# Muller-C3.net
KiCad netlist of a schematic drawn in Altium Designer
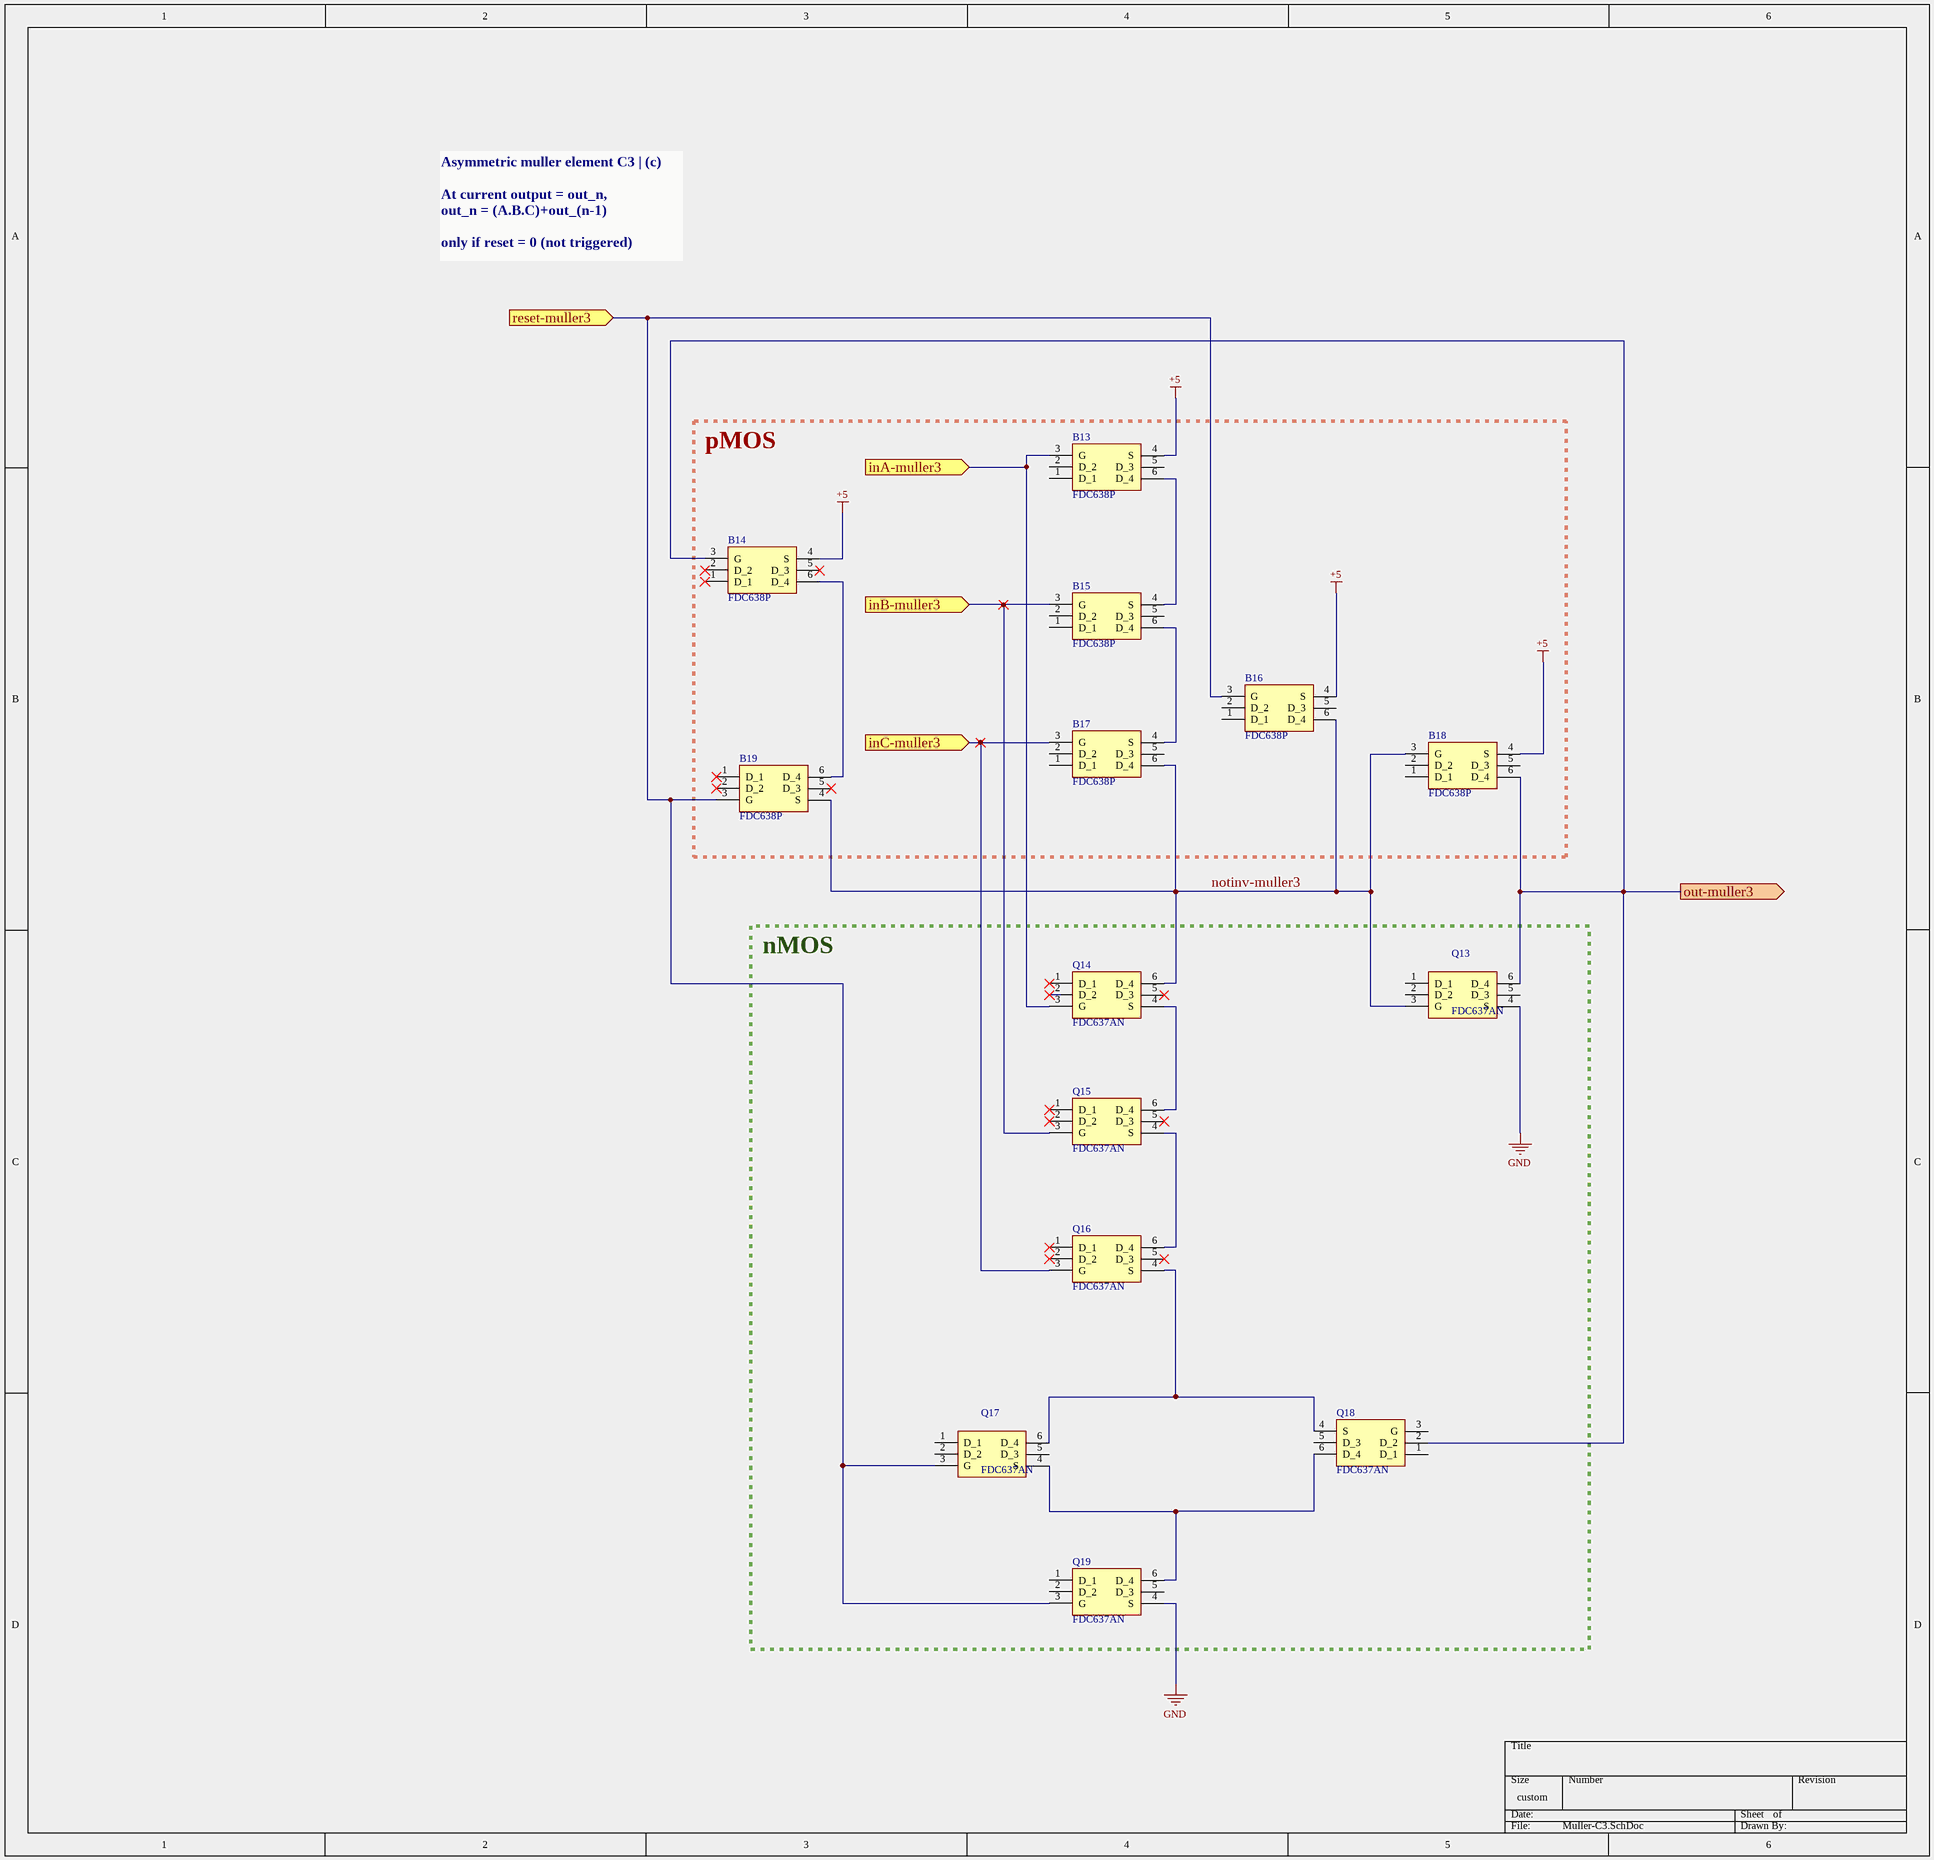
[diagram p0: Muller-C3.SchDoc]

(export (version "E")
  (design (tool "Eeschema 10.0.6"))
  (components
    (comp (ref "B13")
      (value "FDC638P")
      (footprint "SOT95P275X110-6N")
      (description "Low gate charge (10 nC typical)")
      (fields (field (name "MOUSER PART NUMBER") "512-FDC638P"))
      (libsource (lib "iloke") (part "FDC638P"))
    )
    (comp (ref "B14")
      (value "FDC638P")
      (footprint "SOT95P275X110-6N")
      (description "Low gate charge (10 nC typical)")
      (fields (field (name "MOUSER PART NUMBER") "512-FDC638P"))
      (libsource (lib "iloke") (part "FDC638P"))
    )
    (comp (ref "B15")
      (value "FDC638P")
      (footprint "SOT95P275X110-6N")
      (description "Low gate charge (10 nC typical)")
      (fields (field (name "MOUSER PART NUMBER") "512-FDC638P"))
      (libsource (lib "iloke") (part "FDC638P"))
    )
    (comp (ref "B16")
      (value "FDC638P")
      (footprint "SOT95P275X110-6N")
      (description "Low gate charge (10 nC typical)")
      (fields (field (name "MOUSER PART NUMBER") "512-FDC638P"))
      (libsource (lib "iloke") (part "FDC638P"))
    )
    (comp (ref "B17")
      (value "FDC638P")
      (footprint "SOT95P275X110-6N")
      (description "Low gate charge (10 nC typical)")
      (fields (field (name "MOUSER PART NUMBER") "512-FDC638P"))
      (libsource (lib "iloke") (part "FDC638P"))
    )
    (comp (ref "B18")
      (value "FDC638P")
      (footprint "SOT95P275X110-6N")
      (description "Low gate charge (10 nC typical)")
      (fields (field (name "MOUSER PART NUMBER") "512-FDC638P"))
      (libsource (lib "iloke") (part "FDC638P"))
    )
    (comp (ref "B19")
      (value "FDC638P")
      (footprint "SOT95P275X110-6N")
      (description "Low gate charge (10 nC typical)")
      (fields (field (name "MOUSER PART NUMBER") "512-FDC638P"))
      (libsource (lib "") (part "FDC638P_1"))
    )
    (comp (ref "Q13")
      (value "FDC637AN")
      (footprint "SOT95P275X110-6N")
      (description "Low gate charge (10.5nC typical).")
      (fields (field (name "MOUSER PART NUMBER") "512-FDC637AN"))
      (libsource (lib "iloke") (part "FDC637AN"))
    )
    (comp (ref "Q14")
      (value "FDC637AN")
      (footprint "SOT95P275X110-6N")
      (description "Low gate charge (10.5nC typical).")
      (fields (field (name "MOUSER PART NUMBER") "512-FDC637AN"))
      (libsource (lib "iloke") (part "FDC637AN"))
    )
    (comp (ref "Q15")
      (value "FDC637AN")
      (footprint "SOT95P275X110-6N")
      (description "Low gate charge (10.5nC typical).")
      (fields (field (name "MOUSER PART NUMBER") "512-FDC637AN"))
      (libsource (lib "iloke") (part "FDC637AN"))
    )
    (comp (ref "Q16")
      (value "FDC637AN")
      (footprint "SOT95P275X110-6N")
      (description "Low gate charge (10.5nC typical).")
      (fields (field (name "MOUSER PART NUMBER") "512-FDC637AN"))
      (libsource (lib "iloke") (part "FDC637AN"))
    )
    (comp (ref "Q17")
      (value "FDC637AN")
      (footprint "SOT95P275X110-6N")
      (description "Low gate charge (10.5nC typical).")
      (fields (field (name "MOUSER PART NUMBER") "512-FDC637AN"))
      (libsource (lib "iloke") (part "FDC637AN"))
    )
    (comp (ref "Q18")
      (value "FDC637AN")
      (footprint "SOT95P275X110-6N")
      (description "Low gate charge (10.5nC typical).")
      (fields (field (name "MOUSER PART NUMBER") "512-FDC637AN"))
      (libsource (lib "") (part "FDC637AN_1"))
    )
    (comp (ref "Q19")
      (value "FDC637AN")
      (footprint "SOT95P275X110-6N")
      (description "Low gate charge (10.5nC typical).")
      (fields (field (name "MOUSER PART NUMBER") "512-FDC637AN"))
      (libsource (lib "iloke") (part "FDC637AN"))
    )
  )
  (nets
    (net (code "1") (name "+5") (class "Default")
      (node (ref "B13") (pin "4") (pinfunction "S_4") (pintype "passive"))
      (node (ref "B14") (pin "4") (pinfunction "S_4") (pintype "passive"))
      (node (ref "B16") (pin "4") (pinfunction "S_4") (pintype "passive"))
      (node (ref "B18") (pin "4") (pinfunction "S_4") (pintype "passive"))
    )
    (net (code "2") (name "/inA-muller3") (class "Default")
      (node (ref "B13") (pin "3") (pinfunction "G_3") (pintype "passive"))
      (node (ref "Q14") (pin "3") (pinfunction "G_3") (pintype "passive"))
    )
    (net (code "3") (name "/inB-muller3") (class "Default")
      (node (ref "B15") (pin "3") (pinfunction "G_3") (pintype "passive"))
      (node (ref "Q15") (pin "3") (pinfunction "G_3") (pintype "passive"))
    )
    (net (code "4") (name "/inC-muller3") (class "Default")
      (node (ref "B17") (pin "3") (pinfunction "G_3") (pintype "passive"))
      (node (ref "Q16") (pin "3") (pinfunction "G_3") (pintype "passive"))
    )
    (net (code "5") (name "/notinv-muller3") (class "Default")
      (node (ref "B16") (pin "6") (pinfunction "D_4_6") (pintype "passive"))
      (node (ref "B17") (pin "6") (pinfunction "D_4_6") (pintype "passive"))
      (node (ref "B18") (pin "3") (pinfunction "G_3") (pintype "passive"))
      (node (ref "B19") (pin "4") (pinfunction "S_4") (pintype "passive"))
      (node (ref "Q13") (pin "3") (pinfunction "G_3") (pintype "passive"))
      (node (ref "Q14") (pin "6") (pinfunction "D_4_6") (pintype "passive"))
    )
    (net (code "6") (name "/out-muller3") (class "Default")
      (node (ref "B14") (pin "3") (pinfunction "G_3") (pintype "passive"))
      (node (ref "B18") (pin "6") (pinfunction "D_4_6") (pintype "passive"))
      (node (ref "Q13") (pin "6") (pinfunction "D_4_6") (pintype "passive"))
      (node (ref "Q18") (pin "2") (pinfunction "D_2_2") (pintype "passive"))
    )
    (net (code "7") (name "/reset-muller3") (class "Default")
      (node (ref "B16") (pin "3") (pinfunction "G_3") (pintype "passive"))
      (node (ref "B19") (pin "3") (pinfunction "G_3") (pintype "passive"))
      (node (ref "Q17") (pin "3") (pinfunction "G_3") (pintype "passive"))
      (node (ref "Q19") (pin "3") (pinfunction "G_3") (pintype "passive"))
    )
    (net (code "8") (name "GND") (class "Default")
      (node (ref "Q13") (pin "4") (pinfunction "S_4") (pintype "passive"))
      (node (ref "Q19") (pin "4") (pinfunction "S_4") (pintype "passive"))
    )
    (net (code "9") (name "Net-(B13-D_4)") (class "Default")
      (node (ref "B13") (pin "6") (pinfunction "D_4_6") (pintype "passive"))
      (node (ref "B15") (pin "4") (pinfunction "S_4") (pintype "passive"))
    )
    (net (code "10") (name "Net-(B14-D_4)") (class "Default")
      (node (ref "B14") (pin "6") (pinfunction "D_4_6") (pintype "passive"))
      (node (ref "B19") (pin "6") (pinfunction "D_4_6") (pintype "passive"))
    )
    (net (code "11") (name "Net-(B15-D_4)") (class "Default")
      (node (ref "B15") (pin "6") (pinfunction "D_4_6") (pintype "passive"))
      (node (ref "B17") (pin "4") (pinfunction "S_4") (pintype "passive"))
    )
    (net (code "12") (name "Net-(Q14-S)") (class "Default")
      (node (ref "Q14") (pin "4") (pinfunction "S_4") (pintype "passive"))
      (node (ref "Q15") (pin "6") (pinfunction "D_4_6") (pintype "passive"))
    )
    (net (code "13") (name "Net-(Q15-S)") (class "Default")
      (node (ref "Q15") (pin "4") (pinfunction "S_4") (pintype "passive"))
      (node (ref "Q16") (pin "6") (pinfunction "D_4_6") (pintype "passive"))
    )
    (net (code "14") (name "Net-(Q16-S)") (class "Default")
      (node (ref "Q16") (pin "4") (pinfunction "S_4") (pintype "passive"))
      (node (ref "Q17") (pin "6") (pinfunction "D_4_6") (pintype "passive"))
      (node (ref "Q18") (pin "4") (pinfunction "S_4") (pintype "passive"))
    )
    (net (code "15") (name "Net-(Q17-S)") (class "Default")
      (node (ref "Q17") (pin "4") (pinfunction "S_4") (pintype "passive"))
      (node (ref "Q18") (pin "6") (pinfunction "D_4_6") (pintype "passive"))
      (node (ref "Q19") (pin "6") (pinfunction "D_4_6") (pintype "passive"))
    )
    (net (code "16") (name "unconnected-(B13-D_1-Pad1)") (class "Default")
      (node (ref "B13") (pin "1") (pinfunction "D_1_1") (pintype "passive"))
    )
    (net (code "17") (name "unconnected-(B13-D_2-Pad2)") (class "Default")
      (node (ref "B13") (pin "2") (pinfunction "D_2_2") (pintype "passive"))
    )
    (net (code "18") (name "unconnected-(B13-D_3-Pad5)") (class "Default")
      (node (ref "B13") (pin "5") (pinfunction "D_3_5") (pintype "passive"))
    )
    (net (code "19") (name "unconnected-(B14-D_1-Pad1)") (class "Default")
      (node (ref "B14") (pin "1") (pinfunction "D_1_1") (pintype "passive+no_connect"))
    )
    (net (code "20") (name "unconnected-(B14-D_2-Pad2)") (class "Default")
      (node (ref "B14") (pin "2") (pinfunction "D_2_2") (pintype "passive+no_connect"))
    )
    (net (code "21") (name "unconnected-(B14-D_3-Pad5)") (class "Default")
      (node (ref "B14") (pin "5") (pinfunction "D_3_5") (pintype "passive+no_connect"))
    )
    (net (code "22") (name "unconnected-(B15-D_1-Pad1)") (class "Default")
      (node (ref "B15") (pin "1") (pinfunction "D_1_1") (pintype "passive"))
    )
    (net (code "23") (name "unconnected-(B15-D_2-Pad2)") (class "Default")
      (node (ref "B15") (pin "2") (pinfunction "D_2_2") (pintype "passive"))
    )
    (net (code "24") (name "unconnected-(B15-D_3-Pad5)") (class "Default")
      (node (ref "B15") (pin "5") (pinfunction "D_3_5") (pintype "passive"))
    )
    (net (code "25") (name "unconnected-(B16-D_1-Pad1)") (class "Default")
      (node (ref "B16") (pin "1") (pinfunction "D_1_1") (pintype "passive"))
    )
    (net (code "26") (name "unconnected-(B16-D_2-Pad2)") (class "Default")
      (node (ref "B16") (pin "2") (pinfunction "D_2_2") (pintype "passive"))
    )
    (net (code "27") (name "unconnected-(B16-D_3-Pad5)") (class "Default")
      (node (ref "B16") (pin "5") (pinfunction "D_3_5") (pintype "passive"))
    )
    (net (code "28") (name "unconnected-(B17-D_1-Pad1)") (class "Default")
      (node (ref "B17") (pin "1") (pinfunction "D_1_1") (pintype "passive"))
    )
    (net (code "29") (name "unconnected-(B17-D_2-Pad2)") (class "Default")
      (node (ref "B17") (pin "2") (pinfunction "D_2_2") (pintype "passive"))
    )
    (net (code "30") (name "unconnected-(B17-D_3-Pad5)") (class "Default")
      (node (ref "B17") (pin "5") (pinfunction "D_3_5") (pintype "passive"))
    )
    (net (code "31") (name "unconnected-(B18-D_1-Pad1)") (class "Default")
      (node (ref "B18") (pin "1") (pinfunction "D_1_1") (pintype "passive"))
    )
    (net (code "32") (name "unconnected-(B18-D_2-Pad2)") (class "Default")
      (node (ref "B18") (pin "2") (pinfunction "D_2_2") (pintype "passive"))
    )
    (net (code "33") (name "unconnected-(B18-D_3-Pad5)") (class "Default")
      (node (ref "B18") (pin "5") (pinfunction "D_3_5") (pintype "passive"))
    )
    (net (code "34") (name "unconnected-(B19-D_1-Pad1)") (class "Default")
      (node (ref "B19") (pin "1") (pinfunction "D_1_1") (pintype "passive+no_connect"))
    )
    (net (code "35") (name "unconnected-(B19-D_2-Pad2)") (class "Default")
      (node (ref "B19") (pin "2") (pinfunction "D_2_2") (pintype "passive+no_connect"))
    )
    (net (code "36") (name "unconnected-(B19-D_3-Pad5)") (class "Default")
      (node (ref "B19") (pin "5") (pinfunction "D_3_5") (pintype "passive+no_connect"))
    )
    (net (code "37") (name "unconnected-(Q13-D_1-Pad1)") (class "Default")
      (node (ref "Q13") (pin "1") (pinfunction "D_1_1") (pintype "passive"))
    )
    (net (code "38") (name "unconnected-(Q13-D_2-Pad2)") (class "Default")
      (node (ref "Q13") (pin "2") (pinfunction "D_2_2") (pintype "passive"))
    )
    (net (code "39") (name "unconnected-(Q13-D_3-Pad5)") (class "Default")
      (node (ref "Q13") (pin "5") (pinfunction "D_3_5") (pintype "passive"))
    )
    (net (code "40") (name "unconnected-(Q14-D_1-Pad1)") (class "Default")
      (node (ref "Q14") (pin "1") (pinfunction "D_1_1") (pintype "passive+no_connect"))
    )
    (net (code "41") (name "unconnected-(Q14-D_2-Pad2)") (class "Default")
      (node (ref "Q14") (pin "2") (pinfunction "D_2_2") (pintype "passive+no_connect"))
    )
    (net (code "42") (name "unconnected-(Q14-D_3-Pad5)") (class "Default")
      (node (ref "Q14") (pin "5") (pinfunction "D_3_5") (pintype "passive+no_connect"))
    )
    (net (code "43") (name "unconnected-(Q15-D_1-Pad1)") (class "Default")
      (node (ref "Q15") (pin "1") (pinfunction "D_1_1") (pintype "passive+no_connect"))
    )
    (net (code "44") (name "unconnected-(Q15-D_2-Pad2)") (class "Default")
      (node (ref "Q15") (pin "2") (pinfunction "D_2_2") (pintype "passive+no_connect"))
    )
    (net (code "45") (name "unconnected-(Q15-D_3-Pad5)") (class "Default")
      (node (ref "Q15") (pin "5") (pinfunction "D_3_5") (pintype "passive+no_connect"))
    )
    (net (code "46") (name "unconnected-(Q16-D_1-Pad1)") (class "Default")
      (node (ref "Q16") (pin "1") (pinfunction "D_1_1") (pintype "passive+no_connect"))
    )
    (net (code "47") (name "unconnected-(Q16-D_2-Pad2)") (class "Default")
      (node (ref "Q16") (pin "2") (pinfunction "D_2_2") (pintype "passive+no_connect"))
    )
    (net (code "48") (name "unconnected-(Q16-D_3-Pad5)") (class "Default")
      (node (ref "Q16") (pin "5") (pinfunction "D_3_5") (pintype "passive+no_connect"))
    )
    (net (code "49") (name "unconnected-(Q17-D_1-Pad1)") (class "Default")
      (node (ref "Q17") (pin "1") (pinfunction "D_1_1") (pintype "passive"))
    )
    (net (code "50") (name "unconnected-(Q17-D_2-Pad2)") (class "Default")
      (node (ref "Q17") (pin "2") (pinfunction "D_2_2") (pintype "passive"))
    )
    (net (code "51") (name "unconnected-(Q17-D_3-Pad5)") (class "Default")
      (node (ref "Q17") (pin "5") (pinfunction "D_3_5") (pintype "passive"))
    )
    (net (code "52") (name "unconnected-(Q18-D_1-Pad1)") (class "Default")
      (node (ref "Q18") (pin "1") (pinfunction "D_1_1") (pintype "passive"))
    )
    (net (code "53") (name "unconnected-(Q18-D_3-Pad5)") (class "Default")
      (node (ref "Q18") (pin "5") (pinfunction "D_3_5") (pintype "passive"))
    )
    (net (code "54") (name "unconnected-(Q18-G-Pad3)") (class "Default")
      (node (ref "Q18") (pin "3") (pinfunction "G_3") (pintype "passive"))
    )
    (net (code "55") (name "unconnected-(Q19-D_1-Pad1)") (class "Default")
      (node (ref "Q19") (pin "1") (pinfunction "D_1_1") (pintype "passive"))
    )
    (net (code "56") (name "unconnected-(Q19-D_2-Pad2)") (class "Default")
      (node (ref "Q19") (pin "2") (pinfunction "D_2_2") (pintype "passive"))
    )
    (net (code "57") (name "unconnected-(Q19-D_3-Pad5)") (class "Default")
      (node (ref "Q19") (pin "5") (pinfunction "D_3_5") (pintype "passive"))
    )
  )
)
